# Grove_-_Voltage_Divider_v1_0.net
KiCad netlist of a schematic drawn in EAGLE
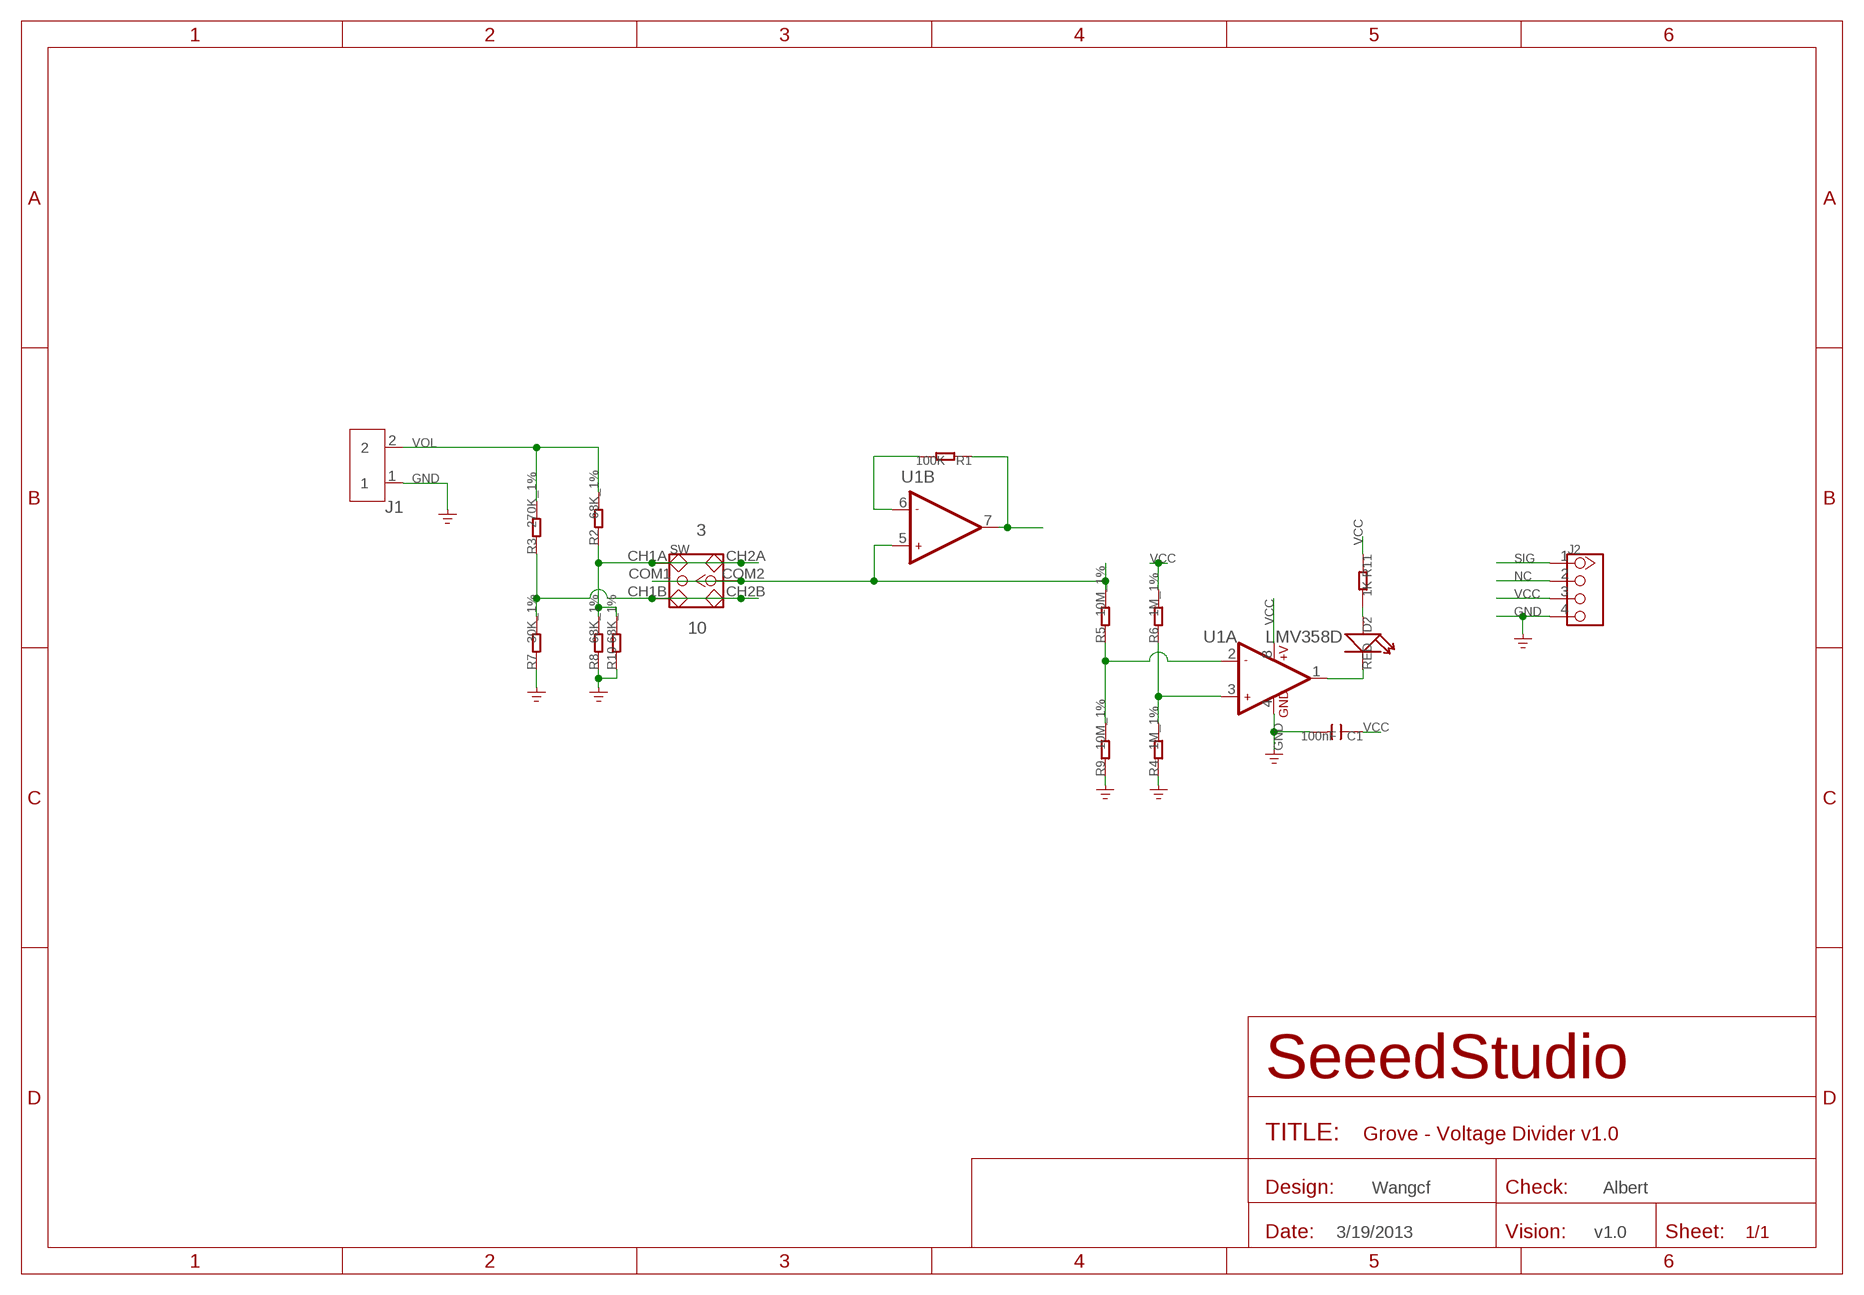
[diagram p0: schematic, sheet 1]

(export (version "E")
  (design (tool "Eeschema 10.0.6"))
  (components
    (comp (ref "C1")
      (value "100nF")
      (footprint "eagle-import:C0603")
      (libsource (lib "eagle-import") (part "C-0603"))
    )
    (comp (ref "D2")
      (value "RED")
      (footprint "eagle-import:LED-0603")
      (libsource (lib "eagle-import") (part "LED'0603'"))
    )
    (comp (ref "J1")
      (value "SCREW-TERMINAL-2P'5.08'")
      (footprint "eagle-import:2P-5.08")
      (libsource (lib "eagle-import") (part "SCREW-TERMINAL-2P'5.08'"))
    )
    (comp (ref "J2")
      (value "TWIG-4P-2.0-2.0")
      (footprint "eagle-import:4P-2.0")
      (libsource (lib "eagle-import") (part "TWIG-4P-2.0-2.0"))
    )
    (comp (ref "R1")
      (value "100K")
      (footprint "eagle-import:R0603")
      (libsource (lib "eagle-import") (part "R-0603"))
    )
    (comp (ref "R2")
      (value "68K_1%")
      (footprint "eagle-import:R0603")
      (libsource (lib "eagle-import") (part "R-0603"))
    )
    (comp (ref "R3")
      (value "270K_1%")
      (footprint "eagle-import:R0603")
      (libsource (lib "eagle-import") (part "R-0603"))
    )
    (comp (ref "R4")
      (value "1M_1%")
      (footprint "eagle-import:R0603")
      (libsource (lib "eagle-import") (part "R-0603"))
    )
    (comp (ref "R5")
      (value "10M_1%")
      (footprint "eagle-import:R0603")
      (libsource (lib "eagle-import") (part "R-0603"))
    )
    (comp (ref "R6")
      (value "1M_1%")
      (footprint "eagle-import:R0603")
      (libsource (lib "eagle-import") (part "R-0603"))
    )
    (comp (ref "R7")
      (value "30K_1%")
      (footprint "eagle-import:R0603")
      (libsource (lib "eagle-import") (part "R-0603"))
    )
    (comp (ref "R8")
      (value "68K_1%")
      (footprint "eagle-import:R0603")
      (libsource (lib "eagle-import") (part "R-0603"))
    )
    (comp (ref "R9")
      (value "10M_1%")
      (footprint "eagle-import:R0603")
      (libsource (lib "eagle-import") (part "R-0603"))
    )
    (comp (ref "R10")
      (value "68K_1%")
      (footprint "eagle-import:R0603")
      (libsource (lib "eagle-import") (part "R-0603"))
    )
    (comp (ref "R11")
      (value "1K")
      (footprint "eagle-import:R0603")
      (libsource (lib "eagle-import") (part "R-0603"))
    )
    (comp (ref "SW")
      (value "SWITCH-2CH-6P'MS-22D18'")
      (footprint "eagle-import:6P-2CH-2.5-9.1X3.5X3.2H")
      (libsource (lib "eagle-import") (part "SWITCH-2CH-6P'MS-22D18'"))
    )
    (comp (ref "U1")
      (value "LMV358D")
      (footprint "eagle-import:SO08")
      (libsource (lib "eagle-import") (part "LMV358D"))
    )
  )
  (nets
    (net (code "1") (name "/NC") (class "Default")
      (node (ref "J2") (pin "2") (pinfunction "2_2") (pintype "bidirectional"))
    )
    (net (code "2") (name "/SIG") (class "Default")
      (node (ref "J2") (pin "1") (pinfunction "1_1") (pintype "bidirectional"))
      (node (ref "R1") (pin "1") (pinfunction "1_1") (pintype "passive"))
      (node (ref "U1") (pin "7") (pinfunction "OUT2_7") (pintype "output"))
    )
    (net (code "3") (name "/VCC") (class "Default")
      (node (ref "C1") (pin "1") (pinfunction "1_1") (pintype "passive"))
      (node (ref "J2") (pin "3") (pinfunction "3_3") (pintype "bidirectional"))
      (node (ref "R11") (pin "1") (pinfunction "1_1") (pintype "passive"))
      (node (ref "R6") (pin "2") (pinfunction "2_2") (pintype "passive"))
      (node (ref "U1") (pin "8") (pinfunction "+V_8") (pintype "power_in"))
    )
    (net (code "4") (name "/VOL") (class "Default")
      (node (ref "J1") (pin "2") (pinfunction "2_2") (pintype "bidirectional"))
      (node (ref "R2") (pin "2") (pinfunction "2_2") (pintype "passive"))
      (node (ref "R3") (pin "2") (pinfunction "2_2") (pintype "passive"))
    )
    (net (code "5") (name "GND_POWER") (class "Default")
      (node (ref "C1") (pin "2") (pinfunction "2_2") (pintype "passive"))
      (node (ref "J1") (pin "1") (pinfunction "1_1") (pintype "bidirectional"))
      (node (ref "J2") (pin "4") (pinfunction "4_4") (pintype "bidirectional"))
      (node (ref "R10") (pin "1") (pinfunction "1_1") (pintype "passive"))
      (node (ref "R4") (pin "1") (pinfunction "1_1") (pintype "passive"))
      (node (ref "R7") (pin "1") (pinfunction "1_1") (pintype "passive"))
      (node (ref "R8") (pin "1") (pinfunction "1_1") (pintype "passive"))
      (node (ref "R9") (pin "1") (pinfunction "1_1") (pintype "passive"))
      (node (ref "U1") (pin "4") (pinfunction "GND_4") (pintype "power_in"))
    )
    (net (code "6") (name "Net-(D2-Pad+)") (class "Default")
      (node (ref "D2") (pin "+") (pinfunction "+_+") (pintype "passive"))
      (node (ref "R11") (pin "2") (pinfunction "2_2") (pintype "passive"))
    )
    (net (code "7") (name "Net-(R3-Pad1)") (class "Default")
      (node (ref "R3") (pin "1") (pinfunction "1_1") (pintype "passive"))
      (node (ref "R7") (pin "2") (pinfunction "2_2") (pintype "passive"))
      (node (ref "SW") (pin "CH1B") (pinfunction "CH1B_CH1B") (pintype "bidirectional"))
      (node (ref "SW") (pin "CH2B") (pinfunction "CH2B_CH2B") (pintype "bidirectional"))
    )
    (net (code "8") (name "Net-(R10-Pad2)") (class "Default")
      (node (ref "R10") (pin "2") (pinfunction "2_2") (pintype "passive"))
      (node (ref "R2") (pin "1") (pinfunction "1_1") (pintype "passive"))
      (node (ref "R8") (pin "2") (pinfunction "2_2") (pintype "passive"))
      (node (ref "SW") (pin "CH1A") (pinfunction "CH1A_CH1A") (pintype "bidirectional"))
      (node (ref "SW") (pin "CH2A") (pinfunction "CH2A_CH2A") (pintype "bidirectional"))
    )
    (net (code "9") (name "Net-(U1A-+IN1)") (class "Default")
      (node (ref "R4") (pin "2") (pinfunction "2_2") (pintype "passive"))
      (node (ref "R6") (pin "1") (pinfunction "1_1") (pintype "passive"))
      (node (ref "U1") (pin "3") (pinfunction "+IN1_3") (pintype "input"))
    )
    (net (code "10") (name "Net-(U1A--IN1)") (class "Default")
      (node (ref "R5") (pin "1") (pinfunction "1_1") (pintype "passive"))
      (node (ref "R9") (pin "2") (pinfunction "2_2") (pintype "passive"))
      (node (ref "U1") (pin "2") (pinfunction "-IN1_2") (pintype "input"))
    )
    (net (code "11") (name "Net-(U1A-OUT1)") (class "Default")
      (node (ref "D2") (pin "-") (pinfunction "-_-") (pintype "passive"))
      (node (ref "U1") (pin "1") (pinfunction "OUT1_1") (pintype "output"))
    )
    (net (code "12") (name "Net-(U1B-+IN2)") (class "Default")
      (node (ref "R5") (pin "2") (pinfunction "2_2") (pintype "passive"))
      (node (ref "SW") (pin "COM1") (pinfunction "COM1_COM1") (pintype "bidirectional"))
      (node (ref "SW") (pin "COM2") (pinfunction "COM2_COM2") (pintype "bidirectional"))
      (node (ref "U1") (pin "5") (pinfunction "+IN2_5") (pintype "input"))
    )
    (net (code "13") (name "Net-(U1B--IN2)") (class "Default")
      (node (ref "R1") (pin "2") (pinfunction "2_2") (pintype "passive"))
      (node (ref "U1") (pin "6") (pinfunction "-IN2_6") (pintype "input"))
    )
  )
)
